# H-mostik.net
KiCad netlist of a schematic drawn in Altium Designer
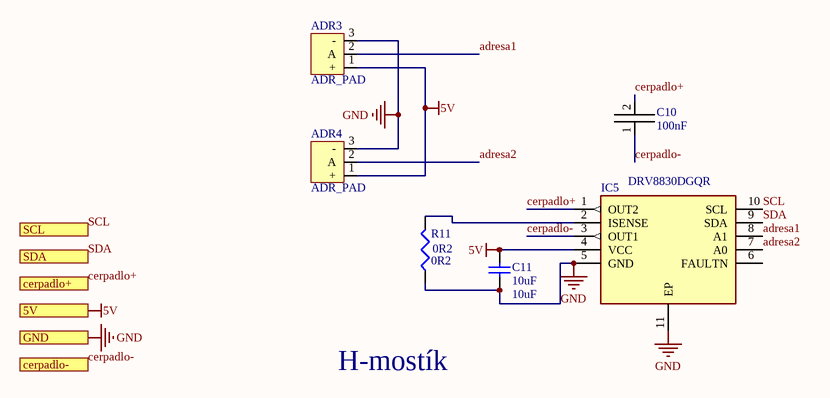
[diagram p0: H-mostik.SchDoc]

(export (version "E")
  (design (tool "Eeschema 10.0.6"))
  (components
    (comp (ref "ADR3")
      (value "ADR_PAD")
      (footprint "SOLDER_PAD")
      (description "ADR PAD 3 PIN")
      (libsource (lib "SCH_Aquatec") (part "ADR_PAD"))
    )
    (comp (ref "ADR4")
      (value "ADR_PAD")
      (footprint "SOLDER_PAD")
      (description "ADR PAD 3 PIN")
      (libsource (lib "SCH_Aquatec") (part "ADR_PAD"))
    )
    (comp (ref "C10")
      (value "100nF")
      (footprint "Capacitor")
      (libsource (lib "SchematicLib_JP") (part "Cap"))
    )
    (comp (ref "C11")
      (value "10uF")
      (footprint "C2512")
      (description "Capacitor (Semiconductor SIM Model)")
      (fields (field (name "ALTIUM_VALUE") "10uF") (field (name "PUBLISHER") "Altium Limited"))
      (libsource (lib "Miscellaneous Devices") (part "Cap Semi"))
    )
    (comp (ref "IC5")
      (value "DRV8830DGQR")
      (footprint "SOP50P490X110-11N")
      (description "Integrated Circuit")
      (fields (field (name "MOUSER PART NUMBER") "595-DRV8830DGQR") (field (name "RS PART NUMBER") "1626149"))
      (libsource (lib "*") (part "DRV8830DGQR"))
    )
    (comp (ref "R11")
      (value "0R2")
      (footprint "J1-0603")
      (description "Resistor")
      (fields (field (name "ALTIUM_VALUE") "0R2") (field (name "PUBLISHER") "Altium Limited"))
      (libsource (lib "Miscellaneous Devices") (part "Res3"))
    )
  )
  (nets
    (net (code "1") (name "/SCL") (class "Default")
      (node (ref "IC5") (pin "10") (pinfunction "SCL_10") (pintype "passive"))
    )
    (net (code "2") (name "/SDA") (class "Default")
      (node (ref "IC5") (pin "9") (pinfunction "SDA_9") (pintype "passive"))
    )
    (net (code "3") (name "/adresa1") (class "Default")
      (node (ref "ADR3") (pin "2") (pinfunction "A_2") (pintype "passive"))
      (node (ref "IC5") (pin "8") (pinfunction "A1_8") (pintype "passive"))
    )
    (net (code "4") (name "/adresa2") (class "Default")
      (node (ref "ADR4") (pin "2") (pinfunction "A_2") (pintype "passive"))
      (node (ref "IC5") (pin "7") (pinfunction "A0_7") (pintype "passive"))
    )
    (net (code "5") (name "/cerpadlo+") (class "Default")
      (node (ref "C10") (pin "2") (pinfunction "2_2") (pintype "passive"))
      (node (ref "IC5") (pin "1") (pinfunction "OUT2_1") (pintype "output"))
    )
    (net (code "6") (name "/cerpadlo-") (class "Default")
      (node (ref "C10") (pin "1") (pinfunction "1_1") (pintype "passive"))
      (node (ref "IC5") (pin "3") (pinfunction "OUT1_3") (pintype "output"))
    )
    (net (code "7") (name "5V") (class "Default")
      (node (ref "ADR3") (pin "1") (pinfunction "+_1") (pintype "passive"))
      (node (ref "ADR4") (pin "1") (pinfunction "+_1") (pintype "passive"))
      (node (ref "C11") (pin "2") (pinfunction "2_2") (pintype "passive"))
      (node (ref "IC5") (pin "4") (pinfunction "VCC_4") (pintype "power_in"))
    )
    (net (code "8") (name "GND") (class "Default")
      (node (ref "ADR3") (pin "3") (pinfunction "-_3") (pintype "passive"))
      (node (ref "ADR4") (pin "3") (pinfunction "-_3") (pintype "passive"))
      (node (ref "C11") (pin "1") (pinfunction "1_1") (pintype "passive"))
      (node (ref "IC5") (pin "11") (pinfunction "EP_11") (pintype "passive"))
      (node (ref "IC5") (pin "5") (pinfunction "GND_5") (pintype "power_in"))
      (node (ref "R11") (pin "1") (pinfunction "1_1") (pintype "passive"))
    )
    (net (code "9") (name "Net-(IC5-ISENSE)") (class "Default")
      (node (ref "IC5") (pin "2") (pinfunction "ISENSE_2") (pintype "passive"))
      (node (ref "R11") (pin "2") (pinfunction "2_2") (pintype "passive"))
    )
    (net (code "10") (name "unconnected-(IC5-FAULTN-Pad6)") (class "Default")
      (node (ref "IC5") (pin "6") (pinfunction "FAULTN_6") (pintype "passive"))
    )
  )
)
